# untitled.net
KiCad netlist of a schematic drawn in EAGLE
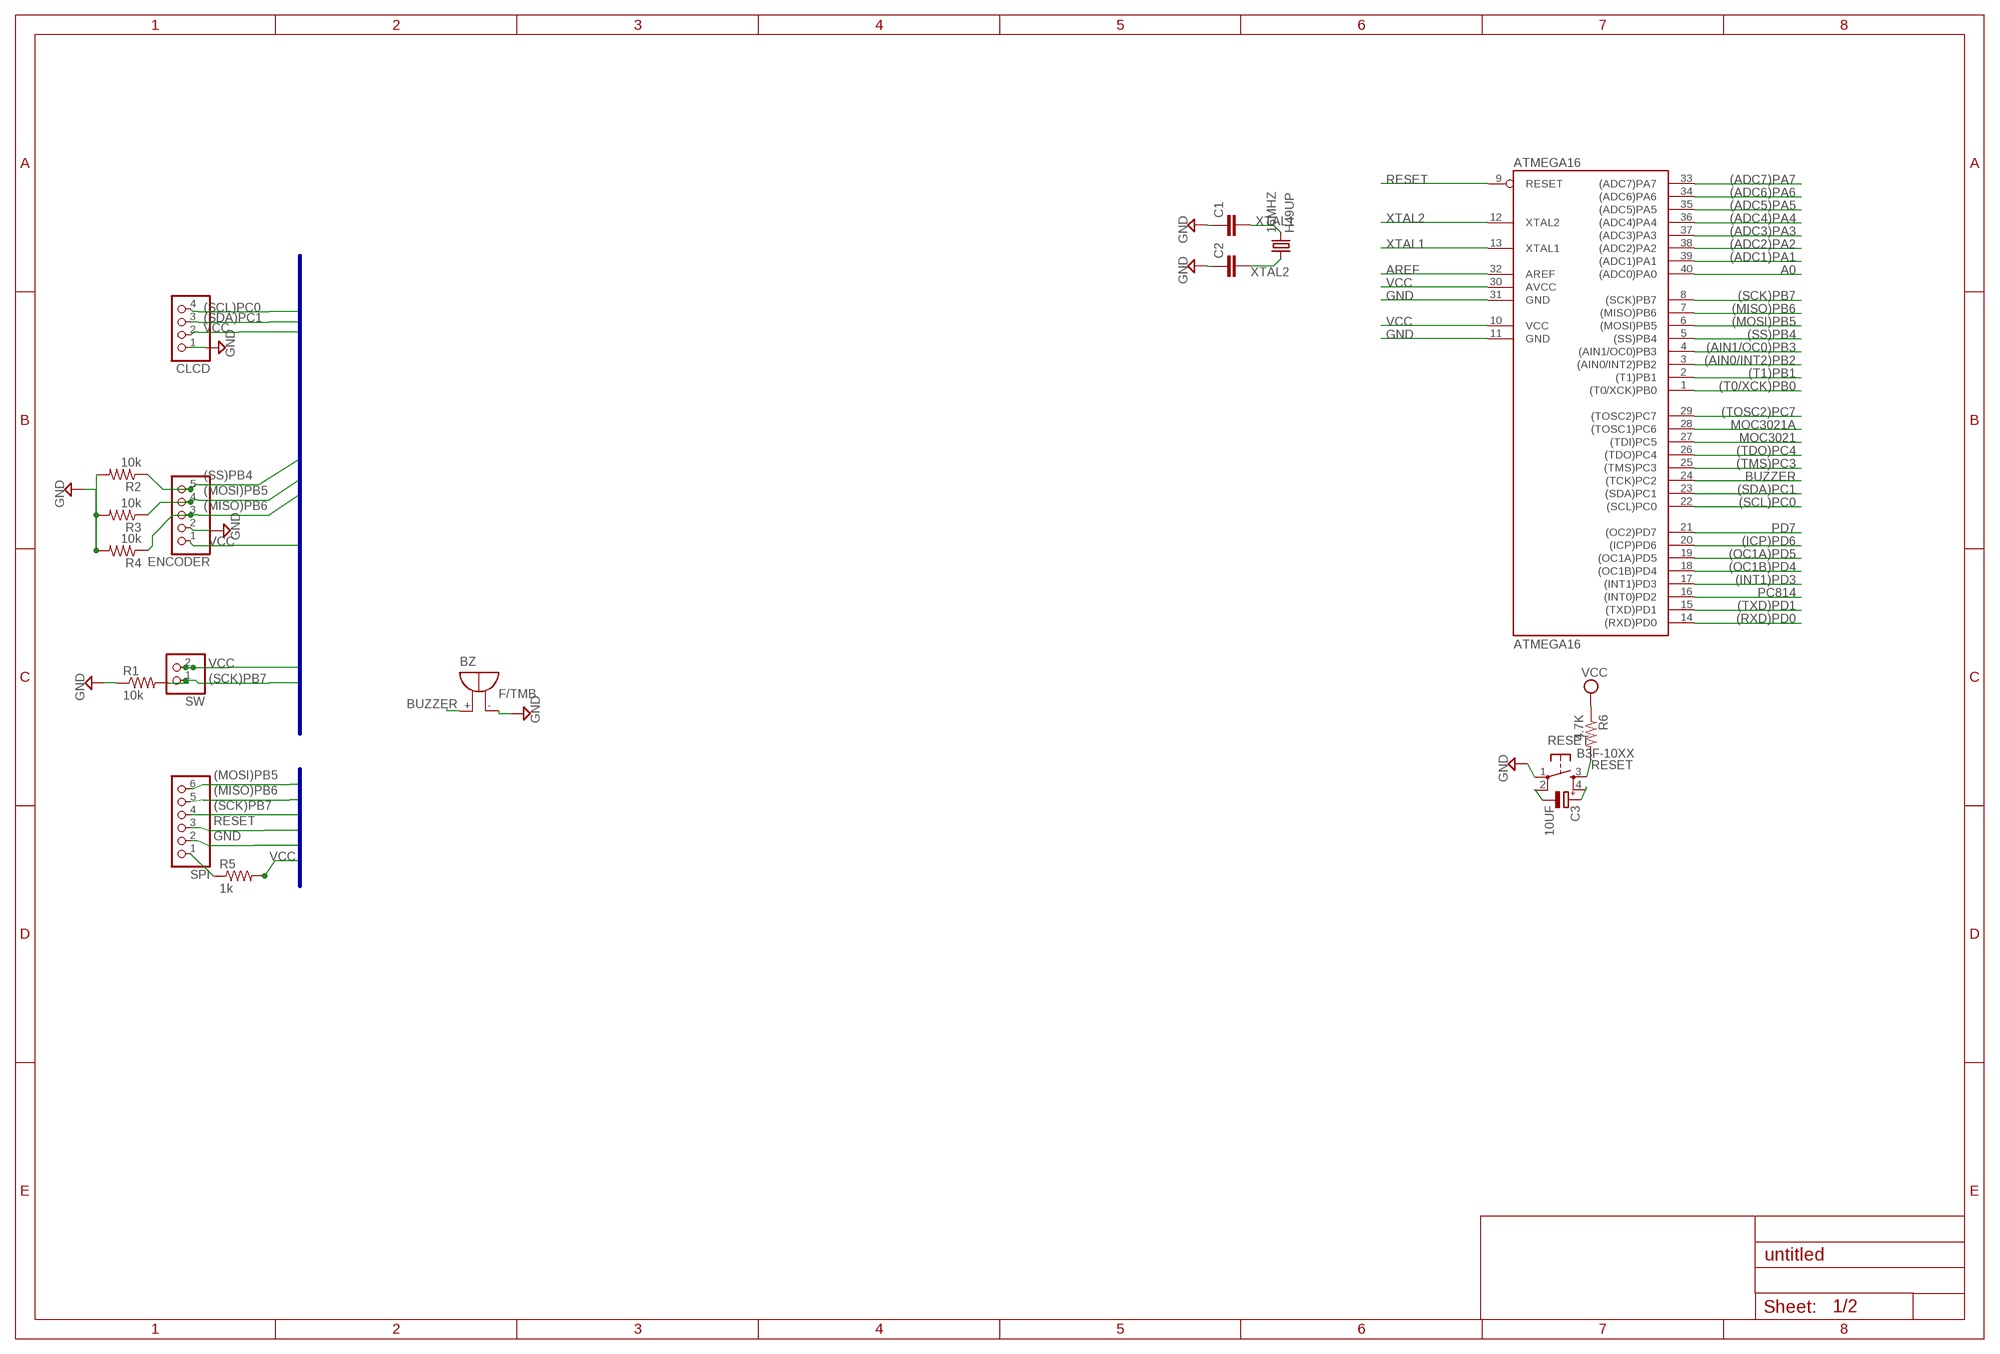
[diagram p0: schematic, sheet 1]
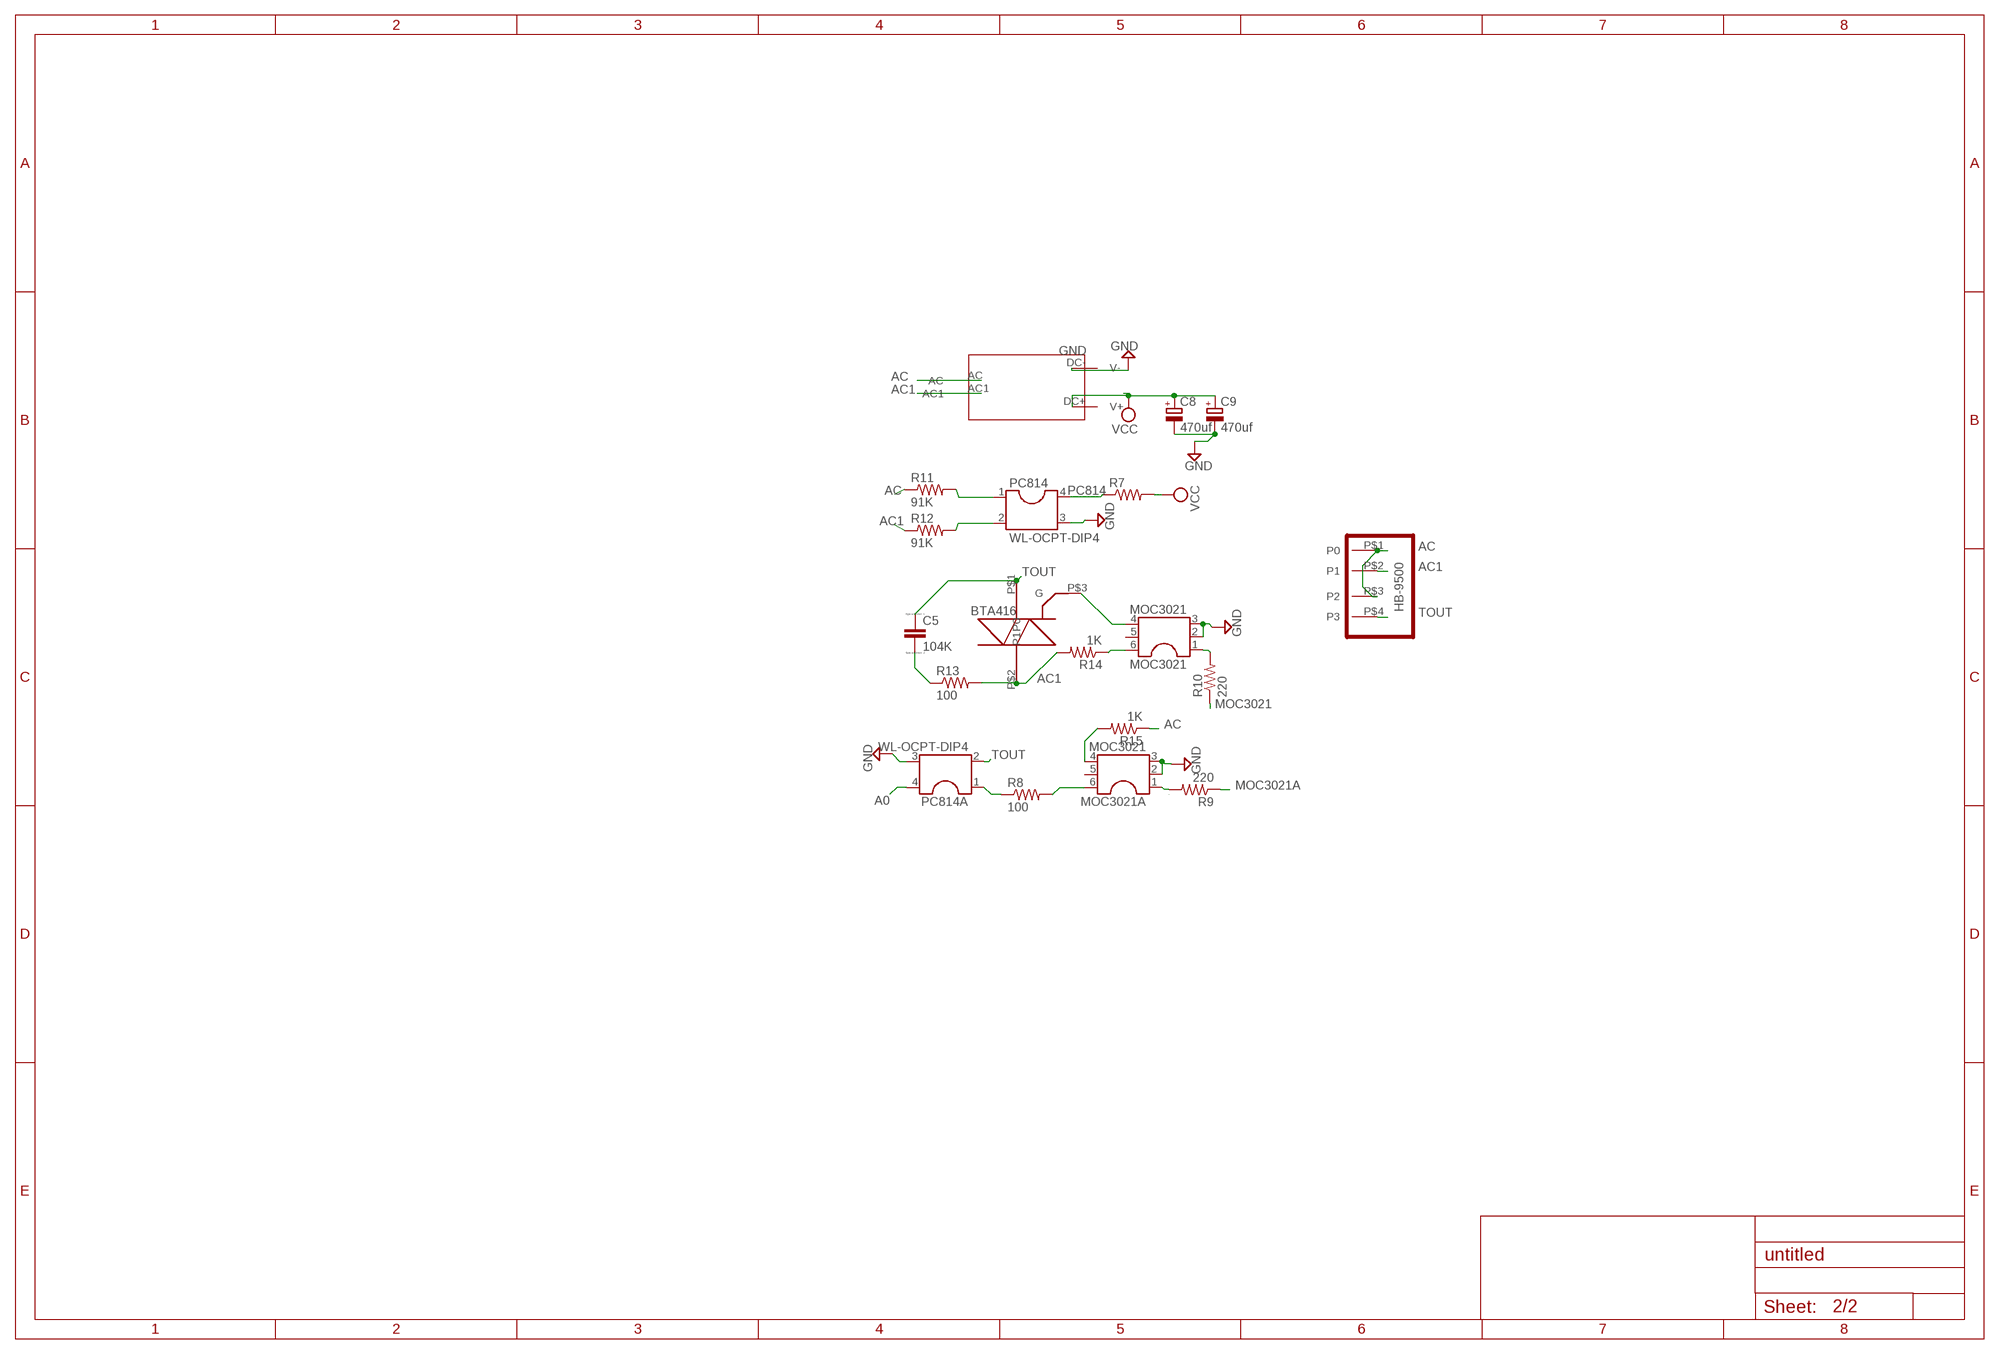
[diagram p1: schematic, sheet 2]

(export (version "E")
  (design (tool "Eeschema 10.0.6"))
  (components
    (comp (ref "BTA416")
      (value "BT41600B")
      (footprint "eagle-import:BT41600B")
      (libsource (lib "eagle-import") (part "BT41600B"))
    )
    (comp (ref "C5")
      (value "104K")
      (footprint "eagle-import:WCAP-FTX2_15X18X5X11(PXLXWXH)")
      (libsource (lib "eagle-import") (part "FTX_15X18X5X11"))
    )
    (comp (ref "C8")
      (value "470uf")
      (footprint "eagle-import:CAPPRD508W65D800H1100B")
      (libsource (lib "eagle-import") (part "CAP-8,5"))
    )
    (comp (ref "C9")
      (value "470uf")
      (footprint "eagle-import:CAPPRD508W65D800H1100B")
      (libsource (lib "eagle-import") (part "CAP-8,5"))
    )
    (comp (ref "HB-9500")
      (value "HB-9500")
      (footprint "eagle-import:HB-9500")
      (libsource (lib "eagle-import") (part "HB-9500"))
    )
    (comp (ref "MOC3021")
      (value "MOC3021")
      (footprint "eagle-import:DIP889W53P254L940H300Q6B")
      (libsource (lib "eagle-import") (part "MOC3021"))
    )
    (comp (ref "MOC3021A")
      (value "MOC3021")
      (footprint "eagle-import:DIP889W53P254L940H300Q6B")
      (libsource (lib "eagle-import") (part "MOC3021"))
    )
    (comp (ref "PC814")
      (value "WL-OCPT-DIP4")
      (footprint "eagle-import:WL-OCPT_DIP4_STANDARD")
      (libsource (lib "eagle-import") (part "WL-OCPT-DIP4"))
    )
    (comp (ref "PC814A")
      (value "WL-OCPT-DIP4")
      (footprint "eagle-import:WL-OCPT_DIP4_STANDARD")
      (libsource (lib "eagle-import") (part "WL-OCPT-DIP4"))
    )
    (comp (ref "R7")
      (value "R-US_0204/7")
      (footprint "eagle-import:0204_7")
      (libsource (lib "eagle-import") (part "R-US_0204/7"))
    )
    (comp (ref "R8")
      (value "100")
      (footprint "eagle-import:0617_17")
      (libsource (lib "eagle-import") (part "R-US_0617/17"))
    )
    (comp (ref "R9")
      (value "220")
      (footprint "eagle-import:0204_7")
      (libsource (lib "eagle-import") (part "R-US_0204/7"))
    )
    (comp (ref "R10")
      (value "220")
      (footprint "eagle-import:0204_7")
      (libsource (lib "eagle-import") (part "R-US_0204/7"))
    )
    (comp (ref "R11")
      (value "91K")
      (footprint "eagle-import:0617_17")
      (libsource (lib "eagle-import") (part "R-US_0617/17"))
    )
    (comp (ref "R12")
      (value "91K")
      (footprint "eagle-import:0617_17")
      (libsource (lib "eagle-import") (part "R-US_0617/17"))
    )
    (comp (ref "R13")
      (value "100")
      (footprint "eagle-import:0617_17")
      (libsource (lib "eagle-import") (part "R-US_0617/17"))
    )
    (comp (ref "R14")
      (value "1K")
      (footprint "eagle-import:0617_17")
      (libsource (lib "eagle-import") (part "R-US_0617/17"))
    )
    (comp (ref "R15")
      (value "1K")
      (footprint "eagle-import:0617_17")
      (libsource (lib "eagle-import") (part "R-US_0617/17"))
    )
    (comp (ref "U$1")
      (value "HLK-PM01")
      (footprint "eagle-import:HLK-PM01")
      (libsource (lib "eagle-import") (part "HLK-PM01"))
    )
    (comp (ref "16MHZ")
      (value "H49UP")
      (footprint "eagle-import:XTAL1170X490X450N")
      (libsource (lib "eagle-import") (part "H49UP"))
    )
    (comp (ref "ATMEGA16")
      (value "ATMEGA16")
      (footprint "eagle-import:DIL40")
      (fields (field (name "MPN") "ATMEGA32-16PU"))
      (libsource (lib "eagle-import") (part "MEGA32-P"))
    )
    (comp (ref "BZ")
      (value "F/TMB")
      (footprint "eagle-import:F_TMB")
      (libsource (lib "eagle-import") (part "F/TMB"))
    )
    (comp (ref "C1")
      (value "C-EU025-024X044")
      (footprint "eagle-import:C025-024X044")
      (libsource (lib "eagle-import") (part "C-EU025-024X044"))
    )
    (comp (ref "C2")
      (value "C-EU025-024X044")
      (footprint "eagle-import:C025-024X044")
      (libsource (lib "eagle-import") (part "C-EU025-024X044"))
    )
    (comp (ref "C3")
      (value "10UF")
      (footprint "eagle-import:E5-5")
      (libsource (lib "eagle-import") (part "CPOL-EUE5-5"))
    )
    (comp (ref "CLCD")
      (value "PINHD-1X4")
      (footprint "eagle-import:1X04")
      (libsource (lib "eagle-import") (part "PINHD-1X4"))
    )
    (comp (ref "ENCODER")
      (value "PINHD-1X5")
      (footprint "eagle-import:1X05")
      (libsource (lib "eagle-import") (part "PINHD-1X5"))
    )
    (comp (ref "R1")
      (value "10k")
      (footprint "eagle-import:0204_7")
      (libsource (lib "eagle-import") (part "R-US_0204/7"))
    )
    (comp (ref "R2")
      (value "10k")
      (footprint "eagle-import:0204_7")
      (libsource (lib "eagle-import") (part "R-US_0204/7"))
    )
    (comp (ref "R3")
      (value "10k")
      (footprint "eagle-import:0204_7")
      (libsource (lib "eagle-import") (part "R-US_0204/7"))
    )
    (comp (ref "R4")
      (value "10k")
      (footprint "eagle-import:0204_7")
      (libsource (lib "eagle-import") (part "R-US_0204/7"))
    )
    (comp (ref "R5")
      (value "1k")
      (footprint "eagle-import:0204_7")
      (libsource (lib "eagle-import") (part "R-US_0204/7"))
    )
    (comp (ref "R6")
      (value "4.7K")
      (footprint "eagle-import:0204_7")
      (libsource (lib "eagle-import") (part "R-US_0204/7"))
    )
    (comp (ref "RESET")
      (value "B3F-10XX")
      (footprint "eagle-import:B3F-10XX")
      (libsource (lib "eagle-import") (part "B3F-10XX"))
    )
    (comp (ref "SPI")
      (value "PINHD-1X6")
      (footprint "eagle-import:1X06")
      (libsource (lib "eagle-import") (part "PINHD-1X6"))
    )
    (comp (ref "SW")
      (value "PINHD-1X2")
      (footprint "eagle-import:1X02")
      (libsource (lib "eagle-import") (part "PINHD-1X2"))
    )
  )
  (nets
    (net (code "1") (name "(ADC1)PA1") (class "Default")
      (node (ref "ATMEGA16") (pin "39") (pinfunction "(ADC1)PA1_39") (pintype "bidirectional"))
    )
    (net (code "2") (name "(ADC2)PA2") (class "Default")
      (node (ref "ATMEGA16") (pin "38") (pinfunction "(ADC2)PA2_38") (pintype "bidirectional"))
    )
    (net (code "3") (name "(ADC3)PA3") (class "Default")
      (node (ref "ATMEGA16") (pin "37") (pinfunction "(ADC3)PA3_37") (pintype "bidirectional"))
    )
    (net (code "4") (name "(ADC4)PA4") (class "Default")
      (node (ref "ATMEGA16") (pin "36") (pinfunction "(ADC4)PA4_36") (pintype "bidirectional"))
    )
    (net (code "5") (name "(ADC5)PA5") (class "Default")
      (node (ref "ATMEGA16") (pin "35") (pinfunction "(ADC5)PA5_35") (pintype "bidirectional"))
    )
    (net (code "6") (name "(ADC6)PA6") (class "Default")
      (node (ref "ATMEGA16") (pin "34") (pinfunction "(ADC6)PA6_34") (pintype "bidirectional"))
    )
    (net (code "7") (name "(ADC7)PA7") (class "Default")
      (node (ref "ATMEGA16") (pin "33") (pinfunction "(ADC7)PA7_33") (pintype "bidirectional"))
    )
    (net (code "8") (name "(AIN0{slash}INT2)PB2") (class "Default")
      (node (ref "ATMEGA16") (pin "3") (pinfunction "(AIN0/INT2)PB2_3") (pintype "bidirectional"))
    )
    (net (code "9") (name "(AIN1{slash}OC0)PB3") (class "Default")
      (node (ref "ATMEGA16") (pin "4") (pinfunction "(AIN1/OC0)PB3_4") (pintype "bidirectional"))
    )
    (net (code "10") (name "(ICP)PD6") (class "Default")
      (node (ref "ATMEGA16") (pin "20") (pinfunction "(ICP)PD6_20") (pintype "bidirectional"))
    )
    (net (code "11") (name "(INT1)PD3") (class "Default")
      (node (ref "ATMEGA16") (pin "17") (pinfunction "(INT1)PD3_17") (pintype "bidirectional"))
    )
    (net (code "12") (name "(MISO)PB6") (class "Default")
      (node (ref "ATMEGA16") (pin "7") (pinfunction "(MISO)PB6_7") (pintype "bidirectional"))
      (node (ref "ENCODER") (pin "3") (pinfunction "3_3") (pintype "passive"))
      (node (ref "R4") (pin "1") (pinfunction "1_1") (pintype "passive"))
      (node (ref "SPI") (pin "5") (pinfunction "5_5") (pintype "passive"))
    )
    (net (code "13") (name "(MOSI)PB5") (class "Default")
      (node (ref "ATMEGA16") (pin "6") (pinfunction "(MOSI)PB5_6") (pintype "bidirectional"))
      (node (ref "ENCODER") (pin "4") (pinfunction "4_4") (pintype "passive"))
      (node (ref "R3") (pin "1") (pinfunction "1_1") (pintype "passive"))
      (node (ref "SPI") (pin "6") (pinfunction "6_6") (pintype "passive"))
    )
    (net (code "14") (name "(OC1A)PD5") (class "Default")
      (node (ref "ATMEGA16") (pin "19") (pinfunction "(OC1A)PD5_19") (pintype "bidirectional"))
    )
    (net (code "15") (name "(OC1B)PD4") (class "Default")
      (node (ref "ATMEGA16") (pin "18") (pinfunction "(OC1B)PD4_18") (pintype "bidirectional"))
    )
    (net (code "16") (name "(RXD)PD0") (class "Default")
      (node (ref "ATMEGA16") (pin "14") (pinfunction "(RXD)PD0_14") (pintype "bidirectional"))
    )
    (net (code "17") (name "(SCK)PB7") (class "Default")
      (node (ref "ATMEGA16") (pin "8") (pinfunction "(SCK)PB7_8") (pintype "bidirectional"))
      (node (ref "R1") (pin "2") (pinfunction "2_2") (pintype "passive"))
      (node (ref "SPI") (pin "4") (pinfunction "4_4") (pintype "passive"))
      (node (ref "SW") (pin "1") (pinfunction "1_1") (pintype "passive"))
    )
    (net (code "18") (name "(SCL)PC0") (class "Default")
      (node (ref "ATMEGA16") (pin "22") (pinfunction "(SCL)PC0_22") (pintype "bidirectional"))
      (node (ref "CLCD") (pin "4") (pinfunction "4_4") (pintype "passive"))
    )
    (net (code "19") (name "(SDA)PC1") (class "Default")
      (node (ref "ATMEGA16") (pin "23") (pinfunction "(SDA)PC1_23") (pintype "bidirectional"))
      (node (ref "CLCD") (pin "3") (pinfunction "3_3") (pintype "passive"))
    )
    (net (code "20") (name "(SS)PB4") (class "Default")
      (node (ref "ATMEGA16") (pin "5") (pinfunction "(SS)PB4_5") (pintype "bidirectional"))
      (node (ref "ENCODER") (pin "5") (pinfunction "5_5") (pintype "passive"))
      (node (ref "R2") (pin "1") (pinfunction "1_1") (pintype "passive"))
    )
    (net (code "21") (name "(T0{slash}XCK)PB0") (class "Default")
      (node (ref "ATMEGA16") (pin "1") (pinfunction "(T0/XCK)PB0_1") (pintype "bidirectional"))
    )
    (net (code "22") (name "(T1)PB1") (class "Default")
      (node (ref "ATMEGA16") (pin "2") (pinfunction "(T1)PB1_2") (pintype "bidirectional"))
    )
    (net (code "23") (name "(TDO)PC4") (class "Default")
      (node (ref "ATMEGA16") (pin "26") (pinfunction "(TDO)PC4_26") (pintype "bidirectional"))
    )
    (net (code "24") (name "(TMS)PC3") (class "Default")
      (node (ref "ATMEGA16") (pin "25") (pinfunction "(TMS)PC3_25") (pintype "bidirectional"))
    )
    (net (code "25") (name "(TOSC2)PC7") (class "Default")
      (node (ref "ATMEGA16") (pin "29") (pinfunction "(TOSC2)PC7_29") (pintype "bidirectional"))
    )
    (net (code "26") (name "(TXD)PD1") (class "Default")
      (node (ref "ATMEGA16") (pin "15") (pinfunction "(TXD)PD1_15") (pintype "bidirectional"))
    )
    (net (code "27") (name "A0") (class "Default")
      (node (ref "ATMEGA16") (pin "40") (pinfunction "(ADC0)PA0_40") (pintype "bidirectional"))
      (node (ref "PC814A") (pin "4") (pinfunction "4_4") (pintype "passive"))
    )
    (net (code "28") (name "AC") (class "Default")
      (node (ref "HB-9500") (pin "P$1") (pinfunction "P0_P$1") (pintype "bidirectional"))
      (node (ref "HB-9500") (pin "P$3") (pinfunction "P2_P$3") (pintype "bidirectional"))
      (node (ref "R11") (pin "1") (pinfunction "1_1") (pintype "passive"))
      (node (ref "R15") (pin "1") (pinfunction "1_1") (pintype "passive"))
      (node (ref "U$1") (pin "AC") (pinfunction "AC_AC") (pintype "bidirectional"))
    )
    (net (code "29") (name "AC1") (class "Default")
      (node (ref "BTA416") (pin "P$2") (pinfunction "P1_P$2") (pintype "bidirectional"))
      (node (ref "HB-9500") (pin "P$2") (pinfunction "P1_P$2") (pintype "bidirectional"))
      (node (ref "R12") (pin "1") (pinfunction "1_1") (pintype "passive"))
      (node (ref "R13") (pin "2") (pinfunction "2_2") (pintype "passive"))
      (node (ref "R14") (pin "2") (pinfunction "2_2") (pintype "passive"))
      (node (ref "U$1") (pin "AC1") (pinfunction "AC1_AC1") (pintype "bidirectional"))
    )
    (net (code "30") (name "AREF") (class "Default")
      (node (ref "ATMEGA16") (pin "32") (pinfunction "AREF_32") (pintype "passive"))
    )
    (net (code "31") (name "BUZZER") (class "Default")
      (node (ref "ATMEGA16") (pin "24") (pinfunction "(TCK)PC2_24") (pintype "bidirectional"))
      (node (ref "BZ") (pin "+") (pinfunction "+_+") (pintype "passive"))
    )
    (net (code "32") (name "GND") (class "Default")
      (node (ref "ATMEGA16") (pin "11") (pinfunction "GND_11") (pintype "power_in"))
      (node (ref "ATMEGA16") (pin "31") (pinfunction "GND_31") (pintype "power_in"))
      (node (ref "BZ") (pin "-") (pinfunction "-_-") (pintype "passive"))
      (node (ref "C1") (pin "1") (pinfunction "1_1") (pintype "passive"))
      (node (ref "C2") (pin "1") (pinfunction "1_1") (pintype "passive"))
      (node (ref "C8") (pin "2") (pinfunction "-_2") (pintype "passive"))
      (node (ref "C9") (pin "2") (pinfunction "-_2") (pintype "passive"))
      (node (ref "CLCD") (pin "1") (pinfunction "1_1") (pintype "passive"))
      (node (ref "ENCODER") (pin "2") (pinfunction "2_2") (pintype "passive"))
      (node (ref "MOC3021") (pin "2") (pinfunction "2_2") (pintype "passive"))
      (node (ref "MOC3021") (pin "3") (pinfunction "3_3") (pintype "passive"))
      (node (ref "MOC3021A") (pin "2") (pinfunction "2_2") (pintype "passive"))
      (node (ref "MOC3021A") (pin "3") (pinfunction "3_3") (pintype "passive"))
      (node (ref "PC814") (pin "3") (pinfunction "3_3") (pintype "passive"))
      (node (ref "PC814A") (pin "3") (pinfunction "3_3") (pintype "passive"))
      (node (ref "R1") (pin "1") (pinfunction "1_1") (pintype "passive"))
      (node (ref "R2") (pin "2") (pinfunction "2_2") (pintype "passive"))
      (node (ref "R3") (pin "2") (pinfunction "2_2") (pintype "passive"))
      (node (ref "R4") (pin "2") (pinfunction "2_2") (pintype "passive"))
      (node (ref "RESET") (pin "1") (pinfunction "P_1") (pintype "passive"))
      (node (ref "SPI") (pin "2") (pinfunction "2_2") (pintype "passive"))
      (node (ref "U$1") (pin "DC-") (pinfunction "V-_DC-") (pintype "bidirectional"))
    )
    (net (code "33") (name "MOC3021") (class "Default")
      (node (ref "ATMEGA16") (pin "27") (pinfunction "(TDI)PC5_27") (pintype "bidirectional"))
      (node (ref "R10") (pin "1") (pinfunction "1_1") (pintype "passive"))
    )
    (net (code "34") (name "MOC3021A") (class "Default")
      (node (ref "ATMEGA16") (pin "28") (pinfunction "(TOSC1)PC6_28") (pintype "bidirectional"))
      (node (ref "R9") (pin "1") (pinfunction "1_1") (pintype "passive"))
    )
    (net (code "35") (name "Net-(BTA416-G)") (class "Default")
      (node (ref "BTA416") (pin "P$3") (pinfunction "G_P$3") (pintype "bidirectional"))
      (node (ref "MOC3021") (pin "4") (pinfunction "4_4") (pintype "passive"))
    )
    (net (code "36") (name "Net-(C5-Pad2)") (class "Default")
      (node (ref "C5") (pin "2") (pinfunction "2_2") (pintype "passive"))
      (node (ref "R13") (pin "1") (pinfunction "1_1") (pintype "passive"))
    )
    (net (code "37") (name "Net-(MOC3021-Pad1)") (class "Default")
      (node (ref "MOC3021") (pin "1") (pinfunction "1_1") (pintype "passive"))
      (node (ref "R10") (pin "2") (pinfunction "2_2") (pintype "passive"))
    )
    (net (code "38") (name "Net-(MOC3021-Pad6)") (class "Default")
      (node (ref "MOC3021") (pin "6") (pinfunction "6_6") (pintype "passive"))
      (node (ref "R14") (pin "1") (pinfunction "1_1") (pintype "passive"))
    )
    (net (code "39") (name "Net-(MOC3021A-Pad1)") (class "Default")
      (node (ref "MOC3021A") (pin "1") (pinfunction "1_1") (pintype "passive"))
      (node (ref "R9") (pin "2") (pinfunction "2_2") (pintype "passive"))
    )
    (net (code "40") (name "Net-(MOC3021A-Pad4)") (class "Default")
      (node (ref "MOC3021A") (pin "4") (pinfunction "4_4") (pintype "passive"))
      (node (ref "R15") (pin "2") (pinfunction "2_2") (pintype "passive"))
    )
    (net (code "41") (name "Net-(MOC3021A-Pad6)") (class "Default")
      (node (ref "MOC3021A") (pin "6") (pinfunction "6_6") (pintype "passive"))
      (node (ref "R8") (pin "2") (pinfunction "2_2") (pintype "passive"))
    )
    (net (code "42") (name "Net-(PC814-Pad1)") (class "Default")
      (node (ref "PC814") (pin "1") (pinfunction "1_1") (pintype "passive"))
      (node (ref "R11") (pin "2") (pinfunction "2_2") (pintype "passive"))
    )
    (net (code "43") (name "Net-(PC814-Pad2)") (class "Default")
      (node (ref "PC814") (pin "2") (pinfunction "2_2") (pintype "passive"))
      (node (ref "R12") (pin "2") (pinfunction "2_2") (pintype "passive"))
    )
    (net (code "44") (name "Net-(PC814A-Pad1)") (class "Default")
      (node (ref "PC814A") (pin "1") (pinfunction "1_1") (pintype "passive"))
      (node (ref "R8") (pin "1") (pinfunction "1_1") (pintype "passive"))
    )
    (net (code "45") (name "Net-(R5-Pad1)") (class "Default")
      (node (ref "R5") (pin "1") (pinfunction "1_1") (pintype "passive"))
      (node (ref "SPI") (pin "1") (pinfunction "1_1") (pintype "passive"))
    )
    (net (code "46") (name "Net-(RESET-P1)") (class "Default")
      (node (ref "C3") (pin "-") (pinfunction "-_-") (pintype "passive"))
      (node (ref "RESET") (pin "2") (pinfunction "P1_2") (pintype "passive"))
    )
    (net (code "47") (name "Net-(RESET-S1)") (class "Default")
      (node (ref "C3") (pin "+") (pinfunction "+_+") (pintype "passive"))
      (node (ref "RESET") (pin "4") (pinfunction "S1_4") (pintype "passive"))
    )
    (net (code "48") (name "PC814") (class "Default")
      (node (ref "ATMEGA16") (pin "16") (pinfunction "(INT0)PD2_16") (pintype "bidirectional"))
      (node (ref "PC814") (pin "4") (pinfunction "4_4") (pintype "passive"))
      (node (ref "R7") (pin "1") (pinfunction "1_1") (pintype "passive"))
    )
    (net (code "49") (name "PD7") (class "Default")
      (node (ref "ATMEGA16") (pin "21") (pinfunction "(OC2)PD7_21") (pintype "bidirectional"))
    )
    (net (code "50") (name "RESET") (class "Default")
      (node (ref "ATMEGA16") (pin "9") (pinfunction "RESET_9") (pintype "input"))
      (node (ref "R6") (pin "2") (pinfunction "2_2") (pintype "passive"))
      (node (ref "RESET") (pin "3") (pinfunction "S_3") (pintype "passive"))
      (node (ref "SPI") (pin "3") (pinfunction "3_3") (pintype "passive"))
    )
    (net (code "51") (name "TOUT") (class "Default")
      (node (ref "BTA416") (pin "P$1") (pinfunction "P0_P$1") (pintype "bidirectional"))
      (node (ref "C5") (pin "1") (pinfunction "1_1") (pintype "passive"))
      (node (ref "HB-9500") (pin "P$4") (pinfunction "P3_P$4") (pintype "bidirectional"))
      (node (ref "PC814A") (pin "2") (pinfunction "2_2") (pintype "passive"))
    )
    (net (code "52") (name "VCC") (class "Default")
      (node (ref "ATMEGA16") (pin "10") (pinfunction "VCC_10") (pintype "power_in"))
      (node (ref "ATMEGA16") (pin "30") (pinfunction "AVCC_30") (pintype "power_in"))
      (node (ref "C8") (pin "1") (pinfunction "+_1") (pintype "passive"))
      (node (ref "C9") (pin "1") (pinfunction "+_1") (pintype "passive"))
      (node (ref "CLCD") (pin "2") (pinfunction "2_2") (pintype "passive"))
      (node (ref "ENCODER") (pin "1") (pinfunction "1_1") (pintype "passive"))
      (node (ref "R5") (pin "2") (pinfunction "2_2") (pintype "passive"))
      (node (ref "R6") (pin "1") (pinfunction "1_1") (pintype "passive"))
      (node (ref "R7") (pin "2") (pinfunction "2_2") (pintype "passive"))
      (node (ref "SW") (pin "2") (pinfunction "2_2") (pintype "passive"))
      (node (ref "U$1") (pin "DC+") (pinfunction "V+_DC+") (pintype "bidirectional"))
    )
    (net (code "53") (name "XTAL1") (class "Default")
      (node (ref "16MHZ") (pin "2") (pinfunction "2_2") (pintype "passive"))
      (node (ref "ATMEGA16") (pin "13") (pinfunction "XTAL1_13") (pintype "bidirectional"))
      (node (ref "C1") (pin "2") (pinfunction "2_2") (pintype "passive"))
    )
    (net (code "54") (name "XTAL2") (class "Default")
      (node (ref "16MHZ") (pin "1") (pinfunction "1_1") (pintype "passive"))
      (node (ref "ATMEGA16") (pin "12") (pinfunction "XTAL2_12") (pintype "bidirectional"))
      (node (ref "C2") (pin "2") (pinfunction "2_2") (pintype "passive"))
    )
    (net (code "55") (name "unconnected-(MOC3021-Pad5)") (class "Default")
      (node (ref "MOC3021") (pin "5") (pinfunction "5_5") (pintype "passive"))
    )
    (net (code "56") (name "unconnected-(MOC3021A-Pad5)") (class "Default")
      (node (ref "MOC3021A") (pin "5") (pinfunction "5_5") (pintype "passive"))
    )
  )
)
